# power.net
KiCad netlist of a schematic drawn in Altium Designer
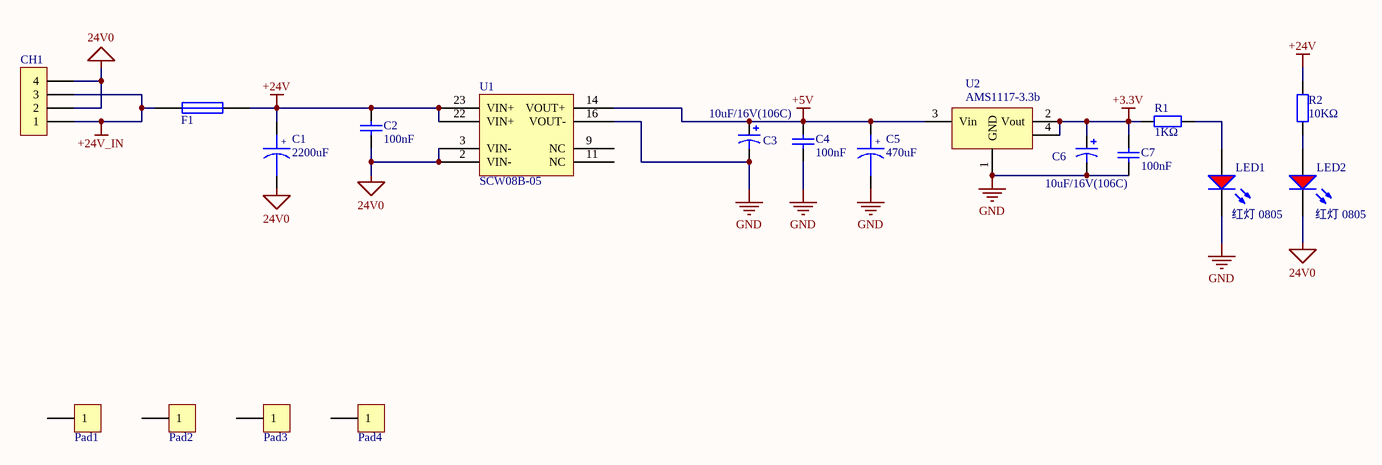
[diagram p0: power.SchDoc]

(export (version "E")
  (design (tool "Eeschema 10.0.6"))
  (components
    (comp (ref "C1")
      (value "2200uF")
      (footprint "C7.8*17")
      (fields (field (name "Comment") "C_2200uF"))
      (libsource (lib "myIntegrated_Library1") (part "C_2200uF"))
    )
    (comp (ref "C2")
      (value "100nF")
      (footprint "0805_C")
      (description "贴片电容")
      (libsource (lib "Miscellaneous Devices LC") (part "0805 100nF(104) 10% 50V"))
    )
    (comp (ref "C3")
      (value "10uF/16V(106C)")
      (footprint "CAP A-3216")
      (description "Polarized Capacitor (Surface Mount)")
      (fields (field (name "Comment") "Cap Pol3b") (field (name "PUBLISHER") "Altium Limited"))
      (libsource (lib "Miscellaneous Devices") (part "Cap Pol3"))
    )
    (comp (ref "C4")
      (value "100nF")
      (footprint "0805_C")
      (description "贴片电容")
      (libsource (lib "Miscellaneous Devices LC") (part "0805 100nF(104) 10% 50V"))
    )
    (comp (ref "C5")
      (value "470uF")
      (footprint "C5*10")
      (fields (field (name "Comment") "C_2200uF"))
      (libsource (lib "myIntegrated_Library1") (part "C_2200uF"))
    )
    (comp (ref "C6")
      (value "10uF/16V(106C)")
      (footprint "CAP A-3216")
      (description "Polarized Capacitor (Surface Mount)")
      (fields (field (name "Comment") "Cap Pol3b") (field (name "PUBLISHER") "Altium Limited"))
      (libsource (lib "Miscellaneous Devices") (part "Cap Pol3"))
    )
    (comp (ref "C7")
      (value "100nF")
      (footprint "0805_C")
      (description "贴片电容")
      (libsource (lib "Miscellaneous Devices LC") (part "0805 100nF(104) 10% 50V"))
    )
    (comp (ref "CH1")
      (value "HEADER1X4")
      (footprint "CH3.96-4PIN")
      (libsource (lib "myIntegrated_Library1") (part "HEADER1X4"))
    )
    (comp (ref "F1")
      (value "FUSE")
      (footprint "X30UF900")
      (libsource (lib "myIntegrated_Library1") (part "FUSE"))
    )
    (comp (ref "LED1")
      (value "红灯 0805")
      (footprint "0805_LED_S1")
      (description "发光二极管")
      (libsource (lib "Miscellaneous Devices LC") (part "0805 红灯"))
    )
    (comp (ref "LED2")
      (value "红灯 0805")
      (footprint "0805_LED_S1")
      (description "发光二极管")
      (libsource (lib "Miscellaneous Devices LC") (part "0805 红灯"))
    )
    (comp (ref "Pad1")
      (value "Pad")
      (footprint "pad35")
      (libsource (lib "myIntegrated_Library1") (part "Pad"))
    )
    (comp (ref "Pad2")
      (value "Pad")
      (footprint "pad35")
      (libsource (lib "myIntegrated_Library1") (part "Pad"))
    )
    (comp (ref "Pad3")
      (value "Pad")
      (footprint "pad35")
      (libsource (lib "myIntegrated_Library1") (part "Pad"))
    )
    (comp (ref "Pad4")
      (value "Pad")
      (footprint "pad35")
      (libsource (lib "myIntegrated_Library1") (part "Pad"))
    )
    (comp (ref "R1")
      (value "1KΩ")
      (footprint "0805_R")
      (description "贴片电阻")
      (libsource (lib "Miscellaneous Devices LC") (part "0805 11KΩ (1102) 1%"))
    )
    (comp (ref "R2")
      (value "10KΩ")
      (footprint "0805_R")
      (description "贴片电阻")
      (libsource (lib "") (part "0805 11KΩ (1102) 1%_1"))
    )
    (comp (ref "U1")
      (value "SCW08B-05")
      (footprint "SCW08B-05")
      (libsource (lib "myIntegrated_Library1") (part "SCW08B-05"))
    )
    (comp (ref "U2")
      (value "AMS1117-3.3b")
      (footprint "SOT223")
      (libsource (lib "货架电子标签元件库") (part "AMS1117-5"))
    )
  )
  (nets
    (net (code "1") (name "+3.3V") (class "Default")
      (node (ref "C6") (pin "1") (pinfunction "1_1") (pintype "passive"))
      (node (ref "C7") (pin "2") (pinfunction "2_2") (pintype "passive"))
      (node (ref "R1") (pin "1") (pinfunction "1_1") (pintype "passive"))
      (node (ref "U2") (pin "2") (pinfunction "Vout_2") (pintype "passive"))
      (node (ref "U2") (pin "4") (pintype "passive"))
    )
    (net (code "2") (name "+5V") (class "Default")
      (node (ref "C3") (pin "1") (pinfunction "1_1") (pintype "passive"))
      (node (ref "C4") (pin "2") (pinfunction "2_2") (pintype "passive"))
      (node (ref "C5") (pin "1") (pinfunction "1_1") (pintype "passive"))
      (node (ref "U1") (pin "14") (pinfunction "VOUT+_14") (pintype "passive"))
      (node (ref "U2") (pin "3") (pinfunction "Vin_3") (pintype "passive"))
    )
    (net (code "3") (name "+24V") (class "Default")
      (node (ref "C1") (pin "1") (pinfunction "1_1") (pintype "passive"))
      (node (ref "C2") (pin "2") (pinfunction "2_2") (pintype "passive"))
      (node (ref "F1") (pin "2") (pinfunction "2_2") (pintype "passive"))
      (node (ref "R2") (pin "2") (pinfunction "2_2") (pintype "passive"))
      (node (ref "U1") (pin "22") (pinfunction "VIN+_22") (pintype "passive"))
      (node (ref "U1") (pin "23") (pinfunction "VIN+_23") (pintype "passive"))
    )
    (net (code "4") (name "+24V_IN") (class "Default")
      (node (ref "CH1") (pin "1") (pinfunction "1_1") (pintype "passive"))
      (node (ref "CH1") (pin "3") (pinfunction "3_3") (pintype "passive"))
      (node (ref "F1") (pin "1") (pinfunction "1_1") (pintype "passive"))
    )
    (net (code "5") (name "24V0") (class "Default")
      (node (ref "C1") (pin "2") (pinfunction "2_2") (pintype "passive"))
      (node (ref "C2") (pin "1") (pinfunction "1_1") (pintype "passive"))
      (node (ref "CH1") (pin "2") (pinfunction "2_2") (pintype "passive"))
      (node (ref "CH1") (pin "4") (pinfunction "4_4") (pintype "passive"))
      (node (ref "LED2") (pin "K") (pinfunction "K_K") (pintype "passive"))
      (node (ref "U1") (pin "2") (pinfunction "VIN-_2") (pintype "passive"))
      (node (ref "U1") (pin "3") (pinfunction "VIN-_3") (pintype "passive"))
    )
    (net (code "6") (name "GND") (class "Default")
      (node (ref "C3") (pin "2") (pinfunction "2_2") (pintype "passive"))
      (node (ref "C4") (pin "1") (pinfunction "1_1") (pintype "passive"))
      (node (ref "C5") (pin "2") (pinfunction "2_2") (pintype "passive"))
      (node (ref "C6") (pin "2") (pinfunction "2_2") (pintype "passive"))
      (node (ref "C7") (pin "1") (pinfunction "1_1") (pintype "passive"))
      (node (ref "LED1") (pin "K") (pinfunction "K_K") (pintype "passive"))
      (node (ref "U1") (pin "16") (pinfunction "VOUT-_16") (pintype "passive"))
      (node (ref "U2") (pin "1") (pinfunction "GND_1") (pintype "passive"))
    )
    (net (code "7") (name "Net-(LED1-PadA)") (class "Default")
      (node (ref "LED1") (pin "A") (pinfunction "A_A") (pintype "passive"))
      (node (ref "R1") (pin "2") (pinfunction "2_2") (pintype "passive"))
    )
    (net (code "8") (name "Net-(LED2-PadA)") (class "Default")
      (node (ref "LED2") (pin "A") (pinfunction "A_A") (pintype "passive"))
      (node (ref "R2") (pin "1") (pinfunction "1_1") (pintype "passive"))
    )
    (net (code "9") (name "unconnected-(Pad1-Pad1)") (class "Default")
      (node (ref "Pad1") (pin "1") (pinfunction "1_1") (pintype "passive"))
    )
    (net (code "10") (name "unconnected-(Pad2-Pad1)") (class "Default")
      (node (ref "Pad2") (pin "1") (pinfunction "1_1") (pintype "passive"))
    )
    (net (code "11") (name "unconnected-(Pad3-Pad1)") (class "Default")
      (node (ref "Pad3") (pin "1") (pinfunction "1_1") (pintype "passive"))
    )
    (net (code "12") (name "unconnected-(Pad4-Pad1)") (class "Default")
      (node (ref "Pad4") (pin "1") (pinfunction "1_1") (pintype "passive"))
    )
    (net (code "13") (name "unconnected-(U1-NC-Pad9)") (class "Default")
      (node (ref "U1") (pin "9") (pinfunction "NC_9") (pintype "passive"))
    )
    (net (code "14") (name "unconnected-(U1-NC-Pad11)") (class "Default")
      (node (ref "U1") (pin "11") (pinfunction "NC_11") (pintype "passive"))
    )
  )
)
